# stm32G031J6M6-Breakout.net
KiCad netlist of a schematic drawn in EAGLE
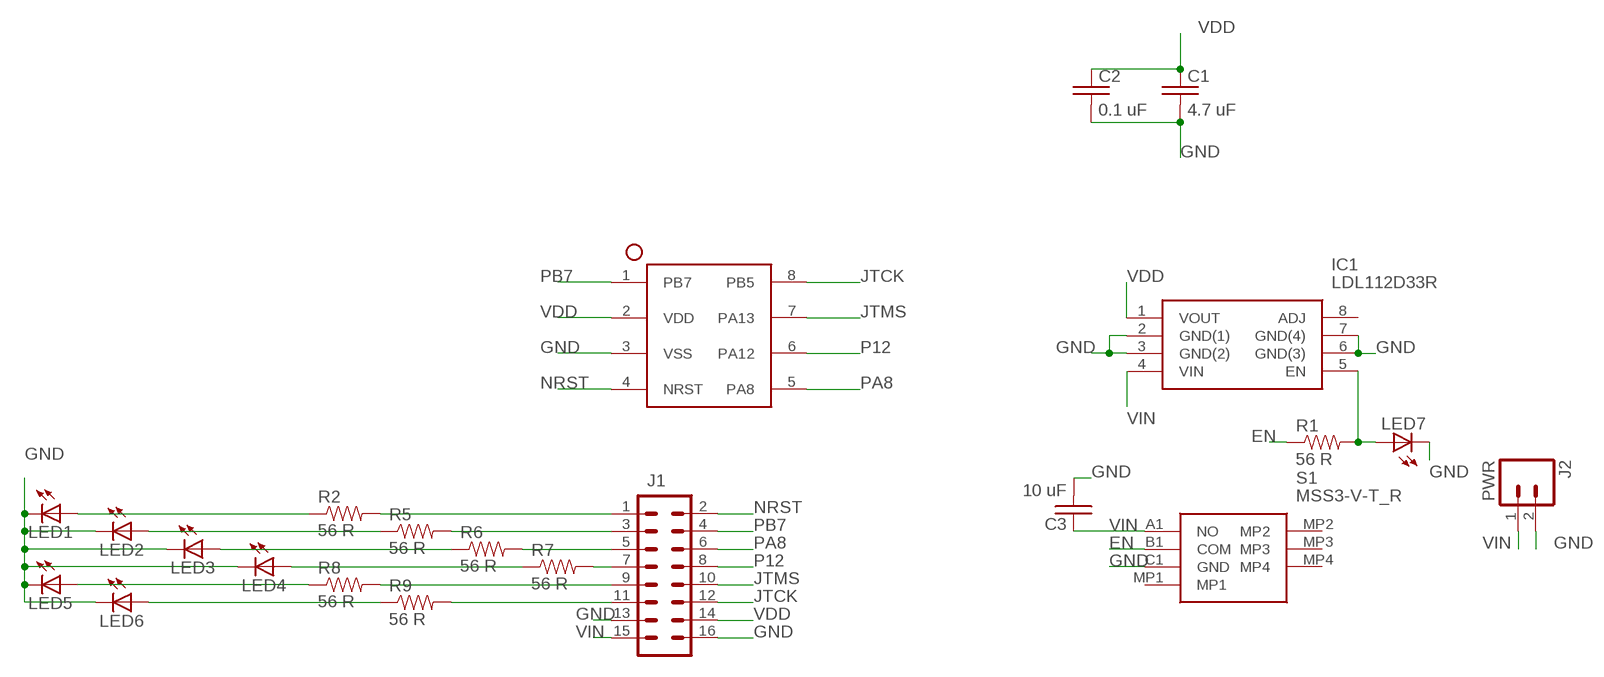
[diagram p0: schematic, sheet 1]

(export (version "E")
  (design (tool "Eeschema 10.0.6"))
  (components
    (comp (ref "C1")
      (value "4.7 uF")
      (footprint "eagle-import:C0805K")
      (libsource (lib "eagle-import") (part "C-USC0805K"))
    )
    (comp (ref "C2")
      (value "0.1 uF")
      (footprint "eagle-import:C0805K")
      (libsource (lib "eagle-import") (part "C-USC0805K"))
    )
    (comp (ref "C3")
      (value "10 uF")
      (footprint "eagle-import:C0805K")
      (libsource (lib "eagle-import") (part "C-USC0805K"))
    )
    (comp (ref "IC1")
      (value "LDL112D33R")
      (footprint "eagle-import:SOIC127P600X175-8N")
      (libsource (lib "eagle-import") (part "LDL112D33R"))
    )
    (comp (ref "J1")
      (value "M08X2")
      (footprint "eagle-import:2X8")
      (libsource (lib "eagle-import") (part "M08X2"))
    )
    (comp (ref "J2")
      (value "PWR")
      (footprint "eagle-import:1X02")
      (libsource (lib "eagle-import") (part "M02PTH"))
    )
    (comp (ref "LED1")
      (value "LED1206")
      (footprint "eagle-import:LED-1206")
      (libsource (lib "eagle-import") (part "LED1206"))
    )
    (comp (ref "LED2")
      (value "LED1206")
      (footprint "eagle-import:LED-1206")
      (libsource (lib "eagle-import") (part "LED1206"))
    )
    (comp (ref "LED3")
      (value "LED1206")
      (footprint "eagle-import:LED-1206")
      (libsource (lib "eagle-import") (part "LED1206"))
    )
    (comp (ref "LED4")
      (value "LED1206")
      (footprint "eagle-import:LED-1206")
      (libsource (lib "eagle-import") (part "LED1206"))
    )
    (comp (ref "LED5")
      (value "LED1206")
      (footprint "eagle-import:LED-1206")
      (libsource (lib "eagle-import") (part "LED1206"))
    )
    (comp (ref "LED6")
      (value "LED1206")
      (footprint "eagle-import:LED-1206")
      (libsource (lib "eagle-import") (part "LED1206"))
    )
    (comp (ref "LED7")
      (value "LED1206")
      (footprint "eagle-import:LED-1206")
      (libsource (lib "eagle-import") (part "LED1206"))
    )
    (comp (ref "R1")
      (value "56 R")
      (footprint "eagle-import:1206")
      (libsource (lib "eagle-import") (part "RESISTOR1206"))
    )
    (comp (ref "R2")
      (value "56 R")
      (footprint "eagle-import:1206")
      (libsource (lib "eagle-import") (part "RESISTOR1206"))
    )
    (comp (ref "R5")
      (value "56 R")
      (footprint "eagle-import:1206")
      (libsource (lib "eagle-import") (part "RESISTOR1206"))
    )
    (comp (ref "R6")
      (value "56 R")
      (footprint "eagle-import:1206")
      (libsource (lib "eagle-import") (part "RESISTOR1206"))
    )
    (comp (ref "R7")
      (value "56 R")
      (footprint "eagle-import:1206")
      (libsource (lib "eagle-import") (part "RESISTOR1206"))
    )
    (comp (ref "R8")
      (value "56 R")
      (footprint "eagle-import:1206")
      (libsource (lib "eagle-import") (part "RESISTOR1206"))
    )
    (comp (ref "R9")
      (value "56 R")
      (footprint "eagle-import:1206")
      (libsource (lib "eagle-import") (part "RESISTOR1206"))
    )
    (comp (ref "S1")
      (value "MSS3-V-T_R")
      (footprint "eagle-import:MSS3VTR")
      (fields
        (field (name "MANUFACTURER_PART_NUMBER") "MSS3-V-T/R")
        (field (name "MOUSER_PART_NUMBER") "113-MSS3-V-T/R")
      )
      (libsource (lib "eagle-import") (part "MSS3-V-T_R"))
    )
    (comp (ref "U$1")
      (value "STM32G031S08N")
      (footprint "eagle-import:SOIC127P600X175-8N")
      (libsource (lib "eagle-import") (part "STM32G031S08N"))
    )
  )
  (nets
    (net (code "1") (name "/EN") (class "Default")
      (node (ref "R1") (pin "1") (pinfunction "1_1") (pintype "passive"))
      (node (ref "S1") (pin "B1") (pinfunction "COM_B1") (pintype "bidirectional"))
    )
    (net (code "2") (name "/GND") (class "Default")
      (node (ref "C1") (pin "2") (pinfunction "2_2") (pintype "passive"))
      (node (ref "C2") (pin "2") (pinfunction "2_2") (pintype "passive"))
      (node (ref "C3") (pin "2") (pinfunction "2_2") (pintype "passive"))
      (node (ref "IC1") (pin "2") (pinfunction "GND(1)_2") (pintype "bidirectional"))
      (node (ref "IC1") (pin "3") (pinfunction "GND(2)_3") (pintype "bidirectional"))
      (node (ref "IC1") (pin "6") (pinfunction "GND(3)_6") (pintype "bidirectional"))
      (node (ref "IC1") (pin "7") (pinfunction "GND(4)_7") (pintype "bidirectional"))
      (node (ref "J1") (pin "13") (pinfunction "13_13") (pintype "passive"))
      (node (ref "J1") (pin "16") (pinfunction "16_16") (pintype "passive"))
      (node (ref "J2") (pin "2") (pinfunction "2_2") (pintype "passive"))
      (node (ref "LED1") (pin "C") (pinfunction "C_C") (pintype "output"))
      (node (ref "LED2") (pin "C") (pinfunction "C_C") (pintype "output"))
      (node (ref "LED3") (pin "C") (pinfunction "C_C") (pintype "output"))
      (node (ref "LED4") (pin "C") (pinfunction "C_C") (pintype "output"))
      (node (ref "LED5") (pin "C") (pinfunction "C_C") (pintype "output"))
      (node (ref "LED6") (pin "C") (pinfunction "C_C") (pintype "output"))
      (node (ref "LED7") (pin "C") (pinfunction "C_C") (pintype "output"))
      (node (ref "S1") (pin "C1") (pinfunction "GND_C1") (pintype "bidirectional"))
      (node (ref "U$1") (pin "3") (pinfunction "VSS_3") (pintype "power_in"))
    )
    (net (code "3") (name "/JTCK") (class "Default")
      (node (ref "J1") (pin "12") (pinfunction "12_12") (pintype "passive"))
      (node (ref "U$1") (pin "8") (pinfunction "PB5_8") (pintype "bidirectional"))
    )
    (net (code "4") (name "/JTMS") (class "Default")
      (node (ref "J1") (pin "10") (pinfunction "10_10") (pintype "passive"))
      (node (ref "U$1") (pin "7") (pinfunction "PA13_7") (pintype "bidirectional"))
    )
    (net (code "5") (name "/NRST") (class "Default")
      (node (ref "J1") (pin "2") (pinfunction "2_2") (pintype "passive"))
      (node (ref "U$1") (pin "4") (pinfunction "NRST_4") (pintype "bidirectional"))
    )
    (net (code "6") (name "/P12") (class "Default")
      (node (ref "J1") (pin "8") (pinfunction "8_8") (pintype "passive"))
      (node (ref "U$1") (pin "6") (pinfunction "PA12_6") (pintype "bidirectional"))
    )
    (net (code "7") (name "/PA8") (class "Default")
      (node (ref "J1") (pin "6") (pinfunction "6_6") (pintype "passive"))
      (node (ref "U$1") (pin "5") (pinfunction "PA8_5") (pintype "bidirectional"))
    )
    (net (code "8") (name "/PB7") (class "Default")
      (node (ref "J1") (pin "4") (pinfunction "4_4") (pintype "passive"))
      (node (ref "U$1") (pin "1") (pinfunction "PB7_1") (pintype "bidirectional"))
    )
    (net (code "9") (name "/VDD") (class "Default")
      (node (ref "C1") (pin "1") (pinfunction "1_1") (pintype "passive"))
      (node (ref "C2") (pin "1") (pinfunction "1_1") (pintype "passive"))
      (node (ref "IC1") (pin "1") (pinfunction "VOUT_1") (pintype "bidirectional"))
      (node (ref "J1") (pin "14") (pinfunction "14_14") (pintype "passive"))
      (node (ref "U$1") (pin "2") (pinfunction "VDD_2") (pintype "power_in"))
    )
    (net (code "10") (name "/VIN") (class "Default")
      (node (ref "C3") (pin "1") (pinfunction "1_1") (pintype "passive"))
      (node (ref "IC1") (pin "4") (pinfunction "VIN_4") (pintype "bidirectional"))
      (node (ref "J1") (pin "15") (pinfunction "15_15") (pintype "passive"))
      (node (ref "J2") (pin "1") (pinfunction "1_1") (pintype "passive"))
      (node (ref "S1") (pin "A1") (pinfunction "NO_A1") (pintype "bidirectional"))
    )
    (net (code "11") (name "Net-(IC1-EN)") (class "Default")
      (node (ref "IC1") (pin "5") (pinfunction "EN_5") (pintype "bidirectional"))
      (node (ref "LED7") (pin "A") (pinfunction "A_A") (pintype "input"))
      (node (ref "R1") (pin "2") (pinfunction "2_2") (pintype "passive"))
    )
    (net (code "12") (name "Net-(J1-Pad1)") (class "Default")
      (node (ref "J1") (pin "1") (pinfunction "1_1") (pintype "passive"))
      (node (ref "R2") (pin "2") (pinfunction "2_2") (pintype "passive"))
    )
    (net (code "13") (name "Net-(J1-Pad3)") (class "Default")
      (node (ref "J1") (pin "3") (pinfunction "3_3") (pintype "passive"))
      (node (ref "R5") (pin "2") (pinfunction "2_2") (pintype "passive"))
    )
    (net (code "14") (name "Net-(J1-Pad5)") (class "Default")
      (node (ref "J1") (pin "5") (pinfunction "5_5") (pintype "passive"))
      (node (ref "R6") (pin "2") (pinfunction "2_2") (pintype "passive"))
    )
    (net (code "15") (name "Net-(J1-Pad7)") (class "Default")
      (node (ref "J1") (pin "7") (pinfunction "7_7") (pintype "passive"))
      (node (ref "R7") (pin "2") (pinfunction "2_2") (pintype "passive"))
    )
    (net (code "16") (name "Net-(J1-Pad9)") (class "Default")
      (node (ref "J1") (pin "9") (pinfunction "9_9") (pintype "passive"))
      (node (ref "R8") (pin "2") (pinfunction "2_2") (pintype "passive"))
    )
    (net (code "17") (name "Net-(J1-Pad11)") (class "Default")
      (node (ref "J1") (pin "11") (pinfunction "11_11") (pintype "passive"))
      (node (ref "R9") (pin "2") (pinfunction "2_2") (pintype "passive"))
    )
    (net (code "18") (name "Net-(LED1-PadA)") (class "Default")
      (node (ref "LED1") (pin "A") (pinfunction "A_A") (pintype "input"))
      (node (ref "R2") (pin "1") (pinfunction "1_1") (pintype "passive"))
    )
    (net (code "19") (name "Net-(LED2-PadA)") (class "Default")
      (node (ref "LED2") (pin "A") (pinfunction "A_A") (pintype "input"))
      (node (ref "R5") (pin "1") (pinfunction "1_1") (pintype "passive"))
    )
    (net (code "20") (name "Net-(LED3-PadA)") (class "Default")
      (node (ref "LED3") (pin "A") (pinfunction "A_A") (pintype "input"))
      (node (ref "R6") (pin "1") (pinfunction "1_1") (pintype "passive"))
    )
    (net (code "21") (name "Net-(LED4-PadA)") (class "Default")
      (node (ref "LED4") (pin "A") (pinfunction "A_A") (pintype "input"))
      (node (ref "R7") (pin "1") (pinfunction "1_1") (pintype "passive"))
    )
    (net (code "22") (name "Net-(LED5-PadA)") (class "Default")
      (node (ref "LED5") (pin "A") (pinfunction "A_A") (pintype "input"))
      (node (ref "R8") (pin "1") (pinfunction "1_1") (pintype "passive"))
    )
    (net (code "23") (name "Net-(LED6-PadA)") (class "Default")
      (node (ref "LED6") (pin "A") (pinfunction "A_A") (pintype "input"))
      (node (ref "R9") (pin "1") (pinfunction "1_1") (pintype "passive"))
    )
    (net (code "24") (name "unconnected-(IC1-ADJ-Pad8)") (class "Default")
      (node (ref "IC1") (pin "8") (pinfunction "ADJ_8") (pintype "bidirectional"))
    )
    (net (code "25") (name "unconnected-(S1-PadMP1)") (class "Default")
      (node (ref "S1") (pin "MP1") (pinfunction "MP1_MP1") (pintype "bidirectional"))
    )
    (net (code "26") (name "unconnected-(S1-PadMP2)") (class "Default")
      (node (ref "S1") (pin "MP2") (pinfunction "MP2_MP2") (pintype "bidirectional"))
    )
    (net (code "27") (name "unconnected-(S1-PadMP3)") (class "Default")
      (node (ref "S1") (pin "MP3") (pinfunction "MP3_MP3") (pintype "bidirectional"))
    )
    (net (code "28") (name "unconnected-(S1-PadMP4)") (class "Default")
      (node (ref "S1") (pin "MP4") (pinfunction "MP4_MP4") (pintype "bidirectional"))
    )
  )
)
